# max21100_v2.net
KiCad netlist of a schematic drawn in EAGLE
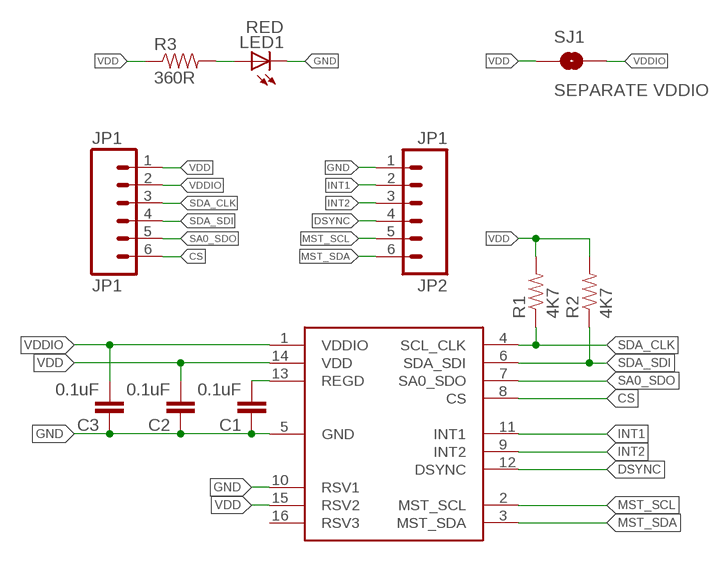
[diagram p0: schematic, sheet 1]

(export (version "E")
  (design (tool "Eeschema 10.0.6"))
  (components
    (comp (ref "C1")
      (value "0.1uF")
      (footprint "eagle-import:0603-CAP")
      (libsource (lib "eagle-import") (part "CAP0603-CAP"))
    )
    (comp (ref "C2")
      (value "0.1uF")
      (footprint "eagle-import:0603-CAP")
      (libsource (lib "eagle-import") (part "CAP0603-CAP"))
    )
    (comp (ref "C3")
      (value "0.1uF")
      (footprint "eagle-import:0603-CAP")
      (libsource (lib "eagle-import") (part "CAP0603-CAP"))
    )
    (comp (ref "JP1")
      (value "JP1")
      (footprint "eagle-import:1X06")
      (libsource (lib "eagle-import") (part "M06SIP"))
    )
    (comp (ref "JP2")
      (value "JP1")
      (footprint "eagle-import:1X06")
      (libsource (lib "eagle-import") (part "M06SIP"))
    )
    (comp (ref "LED1")
      (value "RED")
      (footprint "eagle-import:CHIP-LED0603")
      (libsource (lib "eagle-import") (part "LEDCHIP-LED0603"))
    )
    (comp (ref "R1")
      (value "4K7")
      (footprint "eagle-import:0603-RES")
      (libsource (lib "eagle-import") (part "RESISTOR0603-RES"))
    )
    (comp (ref "R2")
      (value "4K7")
      (footprint "eagle-import:0603-RES")
      (libsource (lib "eagle-import") (part "RESISTOR0603-RES"))
    )
    (comp (ref "R3")
      (value "360R")
      (footprint "eagle-import:0603-RES")
      (libsource (lib "eagle-import") (part "RESISTOR0603-RES"))
    )
    (comp (ref "SJ1")
      (value "SEPARATE VDDIO")
      (footprint "eagle-import:SJ_2S-TRACE")
      (libsource (lib "eagle-import") (part "SOLDERJUMPERTRACE"))
    )
    (comp (ref "U$1")
      (value "MAX21100")
      (footprint "eagle-import:MAX21100")
      (libsource (lib "eagle-import") (part "MAX21100"))
    )
  )
  (nets
    (net (code "1") (name "CS") (class "Default")
      (node (ref "JP1") (pin "6") (pinfunction "6_6") (pintype "passive"))
      (node (ref "U$1") (pin "8") (pinfunction "CS_8") (pintype "bidirectional"))
    )
    (net (code "2") (name "DSYNC") (class "Default")
      (node (ref "JP2") (pin "4") (pinfunction "4_4") (pintype "passive"))
      (node (ref "U$1") (pin "12") (pinfunction "DSYNC_12") (pintype "bidirectional"))
    )
    (net (code "3") (name "GND") (class "Default")
      (node (ref "C1") (pin "1") (pinfunction "1_1") (pintype "passive"))
      (node (ref "C2") (pin "1") (pinfunction "1_1") (pintype "passive"))
      (node (ref "C3") (pin "1") (pinfunction "1_1") (pintype "passive"))
      (node (ref "JP2") (pin "1") (pinfunction "1_1") (pintype "passive"))
      (node (ref "LED1") (pin "C") (pinfunction "C_C") (pintype "passive"))
      (node (ref "U$1") (pin "10") (pinfunction "RSV1_10") (pintype "bidirectional"))
      (node (ref "U$1") (pin "5") (pinfunction "GND_5") (pintype "bidirectional"))
    )
    (net (code "4") (name "INT1") (class "Default")
      (node (ref "JP2") (pin "2") (pinfunction "2_2") (pintype "passive"))
      (node (ref "U$1") (pin "11") (pinfunction "INT1_11") (pintype "bidirectional"))
    )
    (net (code "5") (name "INT2") (class "Default")
      (node (ref "JP2") (pin "3") (pinfunction "3_3") (pintype "passive"))
      (node (ref "U$1") (pin "9") (pinfunction "INT2_9") (pintype "bidirectional"))
    )
    (net (code "6") (name "MST_SCL") (class "Default")
      (node (ref "JP2") (pin "5") (pinfunction "5_5") (pintype "passive"))
      (node (ref "U$1") (pin "2") (pinfunction "MST_SCL_2") (pintype "bidirectional"))
    )
    (net (code "7") (name "MST_SDA") (class "Default")
      (node (ref "JP2") (pin "6") (pinfunction "6_6") (pintype "passive"))
      (node (ref "U$1") (pin "3") (pinfunction "MST_SDA_3") (pintype "bidirectional"))
    )
    (net (code "8") (name "Net-(LED1-PadA)") (class "Default")
      (node (ref "LED1") (pin "A") (pinfunction "A_A") (pintype "passive"))
      (node (ref "R3") (pin "2") (pinfunction "2_2") (pintype "passive"))
    )
    (net (code "9") (name "Net-(U$1-REGD)") (class "Default")
      (node (ref "C1") (pin "2") (pinfunction "2_2") (pintype "passive"))
      (node (ref "U$1") (pin "13") (pinfunction "REGD_13") (pintype "bidirectional"))
    )
    (net (code "10") (name "SA0_SDO") (class "Default")
      (node (ref "JP1") (pin "5") (pinfunction "5_5") (pintype "passive"))
      (node (ref "U$1") (pin "7") (pinfunction "SA0_SDO_7") (pintype "bidirectional"))
    )
    (net (code "11") (name "SDA_CLK") (class "Default")
      (node (ref "JP1") (pin "3") (pinfunction "3_3") (pintype "passive"))
      (node (ref "R1") (pin "1") (pinfunction "1_1") (pintype "passive"))
      (node (ref "U$1") (pin "4") (pinfunction "SCL_CLK_4") (pintype "bidirectional"))
    )
    (net (code "12") (name "SDA_SDI") (class "Default")
      (node (ref "JP1") (pin "4") (pinfunction "4_4") (pintype "passive"))
      (node (ref "R2") (pin "1") (pinfunction "1_1") (pintype "passive"))
      (node (ref "U$1") (pin "6") (pinfunction "SDA_SDI_6") (pintype "bidirectional"))
    )
    (net (code "13") (name "VDD") (class "Default")
      (node (ref "C2") (pin "2") (pinfunction "2_2") (pintype "passive"))
      (node (ref "JP1") (pin "1") (pinfunction "1_1") (pintype "passive"))
      (node (ref "R1") (pin "2") (pinfunction "2_2") (pintype "passive"))
      (node (ref "R2") (pin "2") (pinfunction "2_2") (pintype "passive"))
      (node (ref "R3") (pin "1") (pinfunction "1_1") (pintype "passive"))
      (node (ref "SJ1") (pin "1") (pinfunction "1_1") (pintype "passive"))
      (node (ref "U$1") (pin "14") (pinfunction "VDD_14") (pintype "bidirectional"))
      (node (ref "U$1") (pin "15") (pinfunction "RSV2_15") (pintype "bidirectional"))
    )
    (net (code "14") (name "VDDIO") (class "Default")
      (node (ref "C3") (pin "2") (pinfunction "2_2") (pintype "passive"))
      (node (ref "JP1") (pin "2") (pinfunction "2_2") (pintype "passive"))
      (node (ref "SJ1") (pin "2") (pinfunction "2_2") (pintype "passive"))
      (node (ref "U$1") (pin "1") (pinfunction "VDDIO_1") (pintype "bidirectional"))
    )
    (net (code "15") (name "unconnected-(U$1-RSV3-Pad16)") (class "Default")
      (node (ref "U$1") (pin "16") (pinfunction "RSV3_16") (pintype "bidirectional"))
    )
  )
)
